# r00tzHat.net
KiCad netlist of a schematic drawn in EAGLE
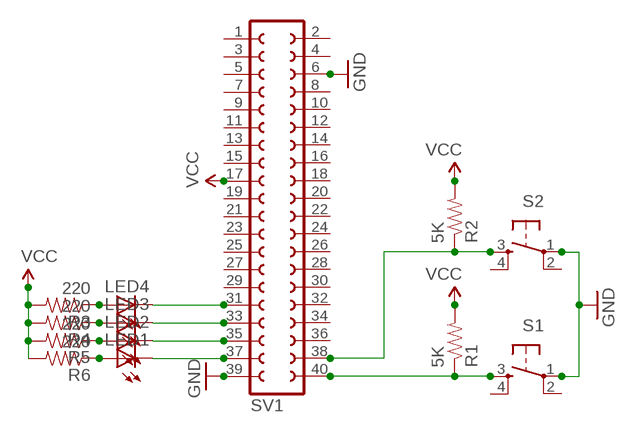
[diagram p0: schematic, sheet 1]

(export (version "E")
  (design (tool "Eeschema 10.0.6"))
  (components
    (comp (ref "LED1")
      (value "LEDCHIPLED_1206")
      (footprint "eagle-import:CHIPLED_1206")
      (libsource (lib "eagle-import") (part "LEDCHIPLED_1206"))
    )
    (comp (ref "LED2")
      (value "LEDCHIPLED_1206")
      (footprint "eagle-import:CHIPLED_1206")
      (libsource (lib "eagle-import") (part "LEDCHIPLED_1206"))
    )
    (comp (ref "LED3")
      (value "LEDCHIPLED_1206")
      (footprint "eagle-import:CHIPLED_1206")
      (libsource (lib "eagle-import") (part "LEDCHIPLED_1206"))
    )
    (comp (ref "LED4")
      (value "LEDCHIPLED_1206")
      (footprint "eagle-import:CHIPLED_1206")
      (libsource (lib "eagle-import") (part "LEDCHIPLED_1206"))
    )
    (comp (ref "R1")
      (value "5K")
      (footprint "eagle-import:0402-RES")
      (libsource (lib "eagle-import") (part "RESISTOR0402-RES"))
    )
    (comp (ref "R2")
      (value "5K")
      (footprint "eagle-import:0402-RES")
      (libsource (lib "eagle-import") (part "RESISTOR0402-RES"))
    )
    (comp (ref "R3")
      (value "220")
      (footprint "eagle-import:0402-RES")
      (libsource (lib "eagle-import") (part "RESISTOR0402-RES"))
    )
    (comp (ref "R4")
      (value "220")
      (footprint "eagle-import:0402-RES")
      (libsource (lib "eagle-import") (part "RESISTOR0402-RES"))
    )
    (comp (ref "R5")
      (value "220")
      (footprint "eagle-import:0402-RES")
      (libsource (lib "eagle-import") (part "RESISTOR0402-RES"))
    )
    (comp (ref "R6")
      (value "220")
      (footprint "eagle-import:0402-RES")
      (libsource (lib "eagle-import") (part "RESISTOR0402-RES"))
    )
    (comp (ref "S1")
      (value "TAC_SWITCHSMD")
      (footprint "eagle-import:TACTILE_SWITCH_SMD")
      (libsource (lib "eagle-import") (part "TAC_SWITCHSMD"))
    )
    (comp (ref "S2")
      (value "TAC_SWITCHSMD")
      (footprint "eagle-import:TACTILE_SWITCH_SMD")
      (libsource (lib "eagle-import") (part "TAC_SWITCHSMD"))
    )
    (comp (ref "SV1")
      (value "FE20-2")
      (footprint "eagle-import:FE20-2")
      (libsource (lib "eagle-import") (part "FE20-2"))
    )
  )
  (nets
    (net (code "1") (name "GND") (class "Default")
      (node (ref "S1") (pin "1") (pinfunction "1_1") (pintype "passive"))
      (node (ref "S2") (pin "1") (pinfunction "1_1") (pintype "passive"))
      (node (ref "SV1") (pin "39") (pinfunction "39_39") (pintype "passive"))
      (node (ref "SV1") (pin "6") (pinfunction "6_6") (pintype "passive"))
    )
    (net (code "2") (name "Net-(LED1-PadA)") (class "Default")
      (node (ref "LED1") (pin "A") (pinfunction "A_A") (pintype "passive"))
      (node (ref "R6") (pin "1") (pinfunction "1_1") (pintype "passive"))
    )
    (net (code "3") (name "Net-(LED1-PadC)") (class "Default")
      (node (ref "LED1") (pin "C") (pinfunction "C_C") (pintype "passive"))
      (node (ref "SV1") (pin "37") (pinfunction "37_37") (pintype "passive"))
    )
    (net (code "4") (name "Net-(LED2-PadA)") (class "Default")
      (node (ref "LED2") (pin "A") (pinfunction "A_A") (pintype "passive"))
      (node (ref "R5") (pin "1") (pinfunction "1_1") (pintype "passive"))
    )
    (net (code "5") (name "Net-(LED2-PadC)") (class "Default")
      (node (ref "LED2") (pin "C") (pinfunction "C_C") (pintype "passive"))
      (node (ref "SV1") (pin "35") (pinfunction "35_35") (pintype "passive"))
    )
    (net (code "6") (name "Net-(LED3-PadA)") (class "Default")
      (node (ref "LED3") (pin "A") (pinfunction "A_A") (pintype "passive"))
      (node (ref "R4") (pin "1") (pinfunction "1_1") (pintype "passive"))
    )
    (net (code "7") (name "Net-(LED3-PadC)") (class "Default")
      (node (ref "LED3") (pin "C") (pinfunction "C_C") (pintype "passive"))
      (node (ref "SV1") (pin "33") (pinfunction "33_33") (pintype "passive"))
    )
    (net (code "8") (name "Net-(LED4-PadA)") (class "Default")
      (node (ref "LED4") (pin "A") (pinfunction "A_A") (pintype "passive"))
      (node (ref "R3") (pin "1") (pinfunction "1_1") (pintype "passive"))
    )
    (net (code "9") (name "Net-(LED4-PadC)") (class "Default")
      (node (ref "LED4") (pin "C") (pinfunction "C_C") (pintype "passive"))
      (node (ref "SV1") (pin "31") (pinfunction "31_31") (pintype "passive"))
    )
    (net (code "10") (name "Net-(R1-Pad1)") (class "Default")
      (node (ref "R1") (pin "1") (pinfunction "1_1") (pintype "passive"))
      (node (ref "S1") (pin "3") (pinfunction "3_3") (pintype "passive"))
      (node (ref "SV1") (pin "40") (pinfunction "40_40") (pintype "passive"))
    )
    (net (code "11") (name "Net-(R2-Pad1)") (class "Default")
      (node (ref "R2") (pin "1") (pinfunction "1_1") (pintype "passive"))
      (node (ref "S2") (pin "3") (pinfunction "3_3") (pintype "passive"))
      (node (ref "SV1") (pin "38") (pinfunction "38_38") (pintype "passive"))
    )
    (net (code "12") (name "VCC") (class "Default")
      (node (ref "R1") (pin "2") (pinfunction "2_2") (pintype "passive"))
      (node (ref "R2") (pin "2") (pinfunction "2_2") (pintype "passive"))
      (node (ref "R3") (pin "2") (pinfunction "2_2") (pintype "passive"))
      (node (ref "R4") (pin "2") (pinfunction "2_2") (pintype "passive"))
      (node (ref "R5") (pin "2") (pinfunction "2_2") (pintype "passive"))
      (node (ref "R6") (pin "2") (pinfunction "2_2") (pintype "passive"))
      (node (ref "SV1") (pin "17") (pinfunction "17_17") (pintype "passive"))
    )
    (net (code "13") (name "unconnected-(S1-Pad2)") (class "Default")
      (node (ref "S1") (pin "2") (pinfunction "2_2") (pintype "passive"))
    )
    (net (code "14") (name "unconnected-(S1-Pad4)") (class "Default")
      (node (ref "S1") (pin "4") (pinfunction "4_4") (pintype "passive"))
    )
    (net (code "15") (name "unconnected-(S2-Pad2)") (class "Default")
      (node (ref "S2") (pin "2") (pinfunction "2_2") (pintype "passive"))
    )
    (net (code "16") (name "unconnected-(S2-Pad4)") (class "Default")
      (node (ref "S2") (pin "4") (pinfunction "4_4") (pintype "passive"))
    )
    (net (code "17") (name "unconnected-(SV1-Pad1)") (class "Default")
      (node (ref "SV1") (pin "1") (pinfunction "1_1") (pintype "passive"))
    )
    (net (code "18") (name "unconnected-(SV1-Pad2)") (class "Default")
      (node (ref "SV1") (pin "2") (pinfunction "2_2") (pintype "passive"))
    )
    (net (code "19") (name "unconnected-(SV1-Pad3)") (class "Default")
      (node (ref "SV1") (pin "3") (pinfunction "3_3") (pintype "passive"))
    )
    (net (code "20") (name "unconnected-(SV1-Pad4)") (class "Default")
      (node (ref "SV1") (pin "4") (pinfunction "4_4") (pintype "passive"))
    )
    (net (code "21") (name "unconnected-(SV1-Pad5)") (class "Default")
      (node (ref "SV1") (pin "5") (pinfunction "5_5") (pintype "passive"))
    )
    (net (code "22") (name "unconnected-(SV1-Pad7)") (class "Default")
      (node (ref "SV1") (pin "7") (pinfunction "7_7") (pintype "passive"))
    )
    (net (code "23") (name "unconnected-(SV1-Pad8)") (class "Default")
      (node (ref "SV1") (pin "8") (pinfunction "8_8") (pintype "passive"))
    )
    (net (code "24") (name "unconnected-(SV1-Pad9)") (class "Default")
      (node (ref "SV1") (pin "9") (pinfunction "9_9") (pintype "passive"))
    )
    (net (code "25") (name "unconnected-(SV1-Pad10)") (class "Default")
      (node (ref "SV1") (pin "10") (pinfunction "10_10") (pintype "passive"))
    )
    (net (code "26") (name "unconnected-(SV1-Pad11)") (class "Default")
      (node (ref "SV1") (pin "11") (pinfunction "11_11") (pintype "passive"))
    )
    (net (code "27") (name "unconnected-(SV1-Pad12)") (class "Default")
      (node (ref "SV1") (pin "12") (pinfunction "12_12") (pintype "passive"))
    )
    (net (code "28") (name "unconnected-(SV1-Pad13)") (class "Default")
      (node (ref "SV1") (pin "13") (pinfunction "13_13") (pintype "passive"))
    )
    (net (code "29") (name "unconnected-(SV1-Pad14)") (class "Default")
      (node (ref "SV1") (pin "14") (pinfunction "14_14") (pintype "passive"))
    )
    (net (code "30") (name "unconnected-(SV1-Pad15)") (class "Default")
      (node (ref "SV1") (pin "15") (pinfunction "15_15") (pintype "passive"))
    )
    (net (code "31") (name "unconnected-(SV1-Pad16)") (class "Default")
      (node (ref "SV1") (pin "16") (pinfunction "16_16") (pintype "passive"))
    )
    (net (code "32") (name "unconnected-(SV1-Pad18)") (class "Default")
      (node (ref "SV1") (pin "18") (pinfunction "18_18") (pintype "passive"))
    )
    (net (code "33") (name "unconnected-(SV1-Pad19)") (class "Default")
      (node (ref "SV1") (pin "19") (pinfunction "19_19") (pintype "passive"))
    )
    (net (code "34") (name "unconnected-(SV1-Pad20)") (class "Default")
      (node (ref "SV1") (pin "20") (pinfunction "20_20") (pintype "passive"))
    )
    (net (code "35") (name "unconnected-(SV1-Pad21)") (class "Default")
      (node (ref "SV1") (pin "21") (pinfunction "21_21") (pintype "passive"))
    )
    (net (code "36") (name "unconnected-(SV1-Pad22)") (class "Default")
      (node (ref "SV1") (pin "22") (pinfunction "22_22") (pintype "passive"))
    )
    (net (code "37") (name "unconnected-(SV1-Pad23)") (class "Default")
      (node (ref "SV1") (pin "23") (pinfunction "23_23") (pintype "passive"))
    )
    (net (code "38") (name "unconnected-(SV1-Pad24)") (class "Default")
      (node (ref "SV1") (pin "24") (pinfunction "24_24") (pintype "passive"))
    )
    (net (code "39") (name "unconnected-(SV1-Pad25)") (class "Default")
      (node (ref "SV1") (pin "25") (pinfunction "25_25") (pintype "passive"))
    )
    (net (code "40") (name "unconnected-(SV1-Pad26)") (class "Default")
      (node (ref "SV1") (pin "26") (pinfunction "26_26") (pintype "passive"))
    )
    (net (code "41") (name "unconnected-(SV1-Pad27)") (class "Default")
      (node (ref "SV1") (pin "27") (pinfunction "27_27") (pintype "passive"))
    )
    (net (code "42") (name "unconnected-(SV1-Pad28)") (class "Default")
      (node (ref "SV1") (pin "28") (pinfunction "28_28") (pintype "passive"))
    )
    (net (code "43") (name "unconnected-(SV1-Pad29)") (class "Default")
      (node (ref "SV1") (pin "29") (pinfunction "29_29") (pintype "passive"))
    )
    (net (code "44") (name "unconnected-(SV1-Pad30)") (class "Default")
      (node (ref "SV1") (pin "30") (pinfunction "30_30") (pintype "passive"))
    )
    (net (code "45") (name "unconnected-(SV1-Pad32)") (class "Default")
      (node (ref "SV1") (pin "32") (pinfunction "32_32") (pintype "passive"))
    )
    (net (code "46") (name "unconnected-(SV1-Pad34)") (class "Default")
      (node (ref "SV1") (pin "34") (pinfunction "34_34") (pintype "passive"))
    )
    (net (code "47") (name "unconnected-(SV1-Pad36)") (class "Default")
      (node (ref "SV1") (pin "36") (pinfunction "36_36") (pintype "passive"))
    )
  )
)
